# PX4FLOW2_1_CPU_X0.net
KiCad netlist of a schematic drawn in Altium Designer
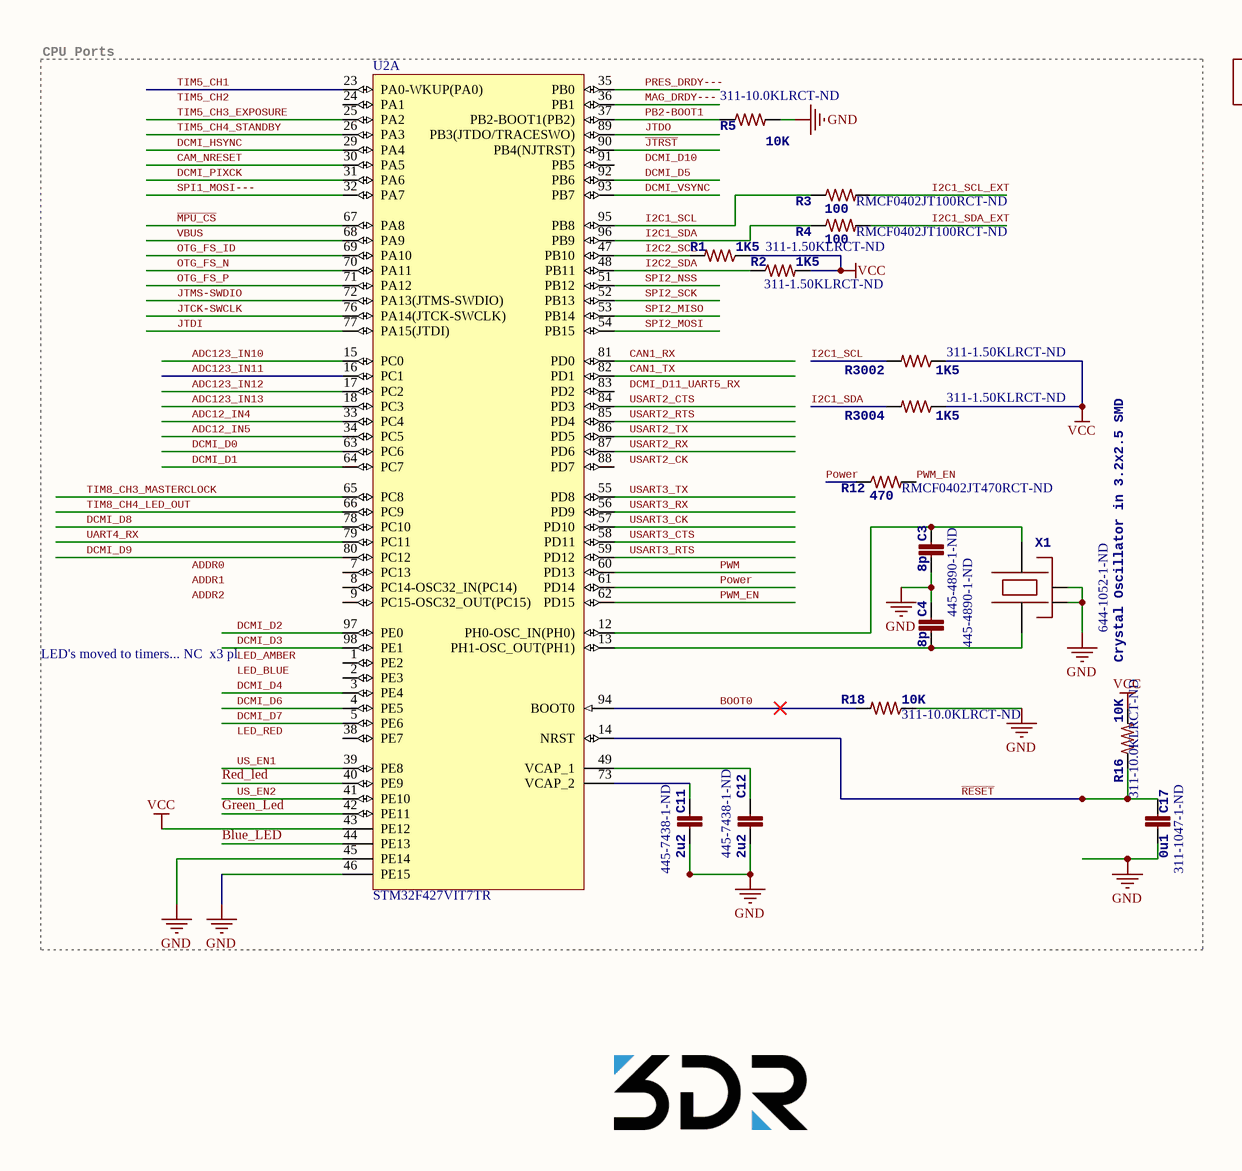
[diagram p0: PX4FLOW2.1_CPU_X0.SchDoc, left]
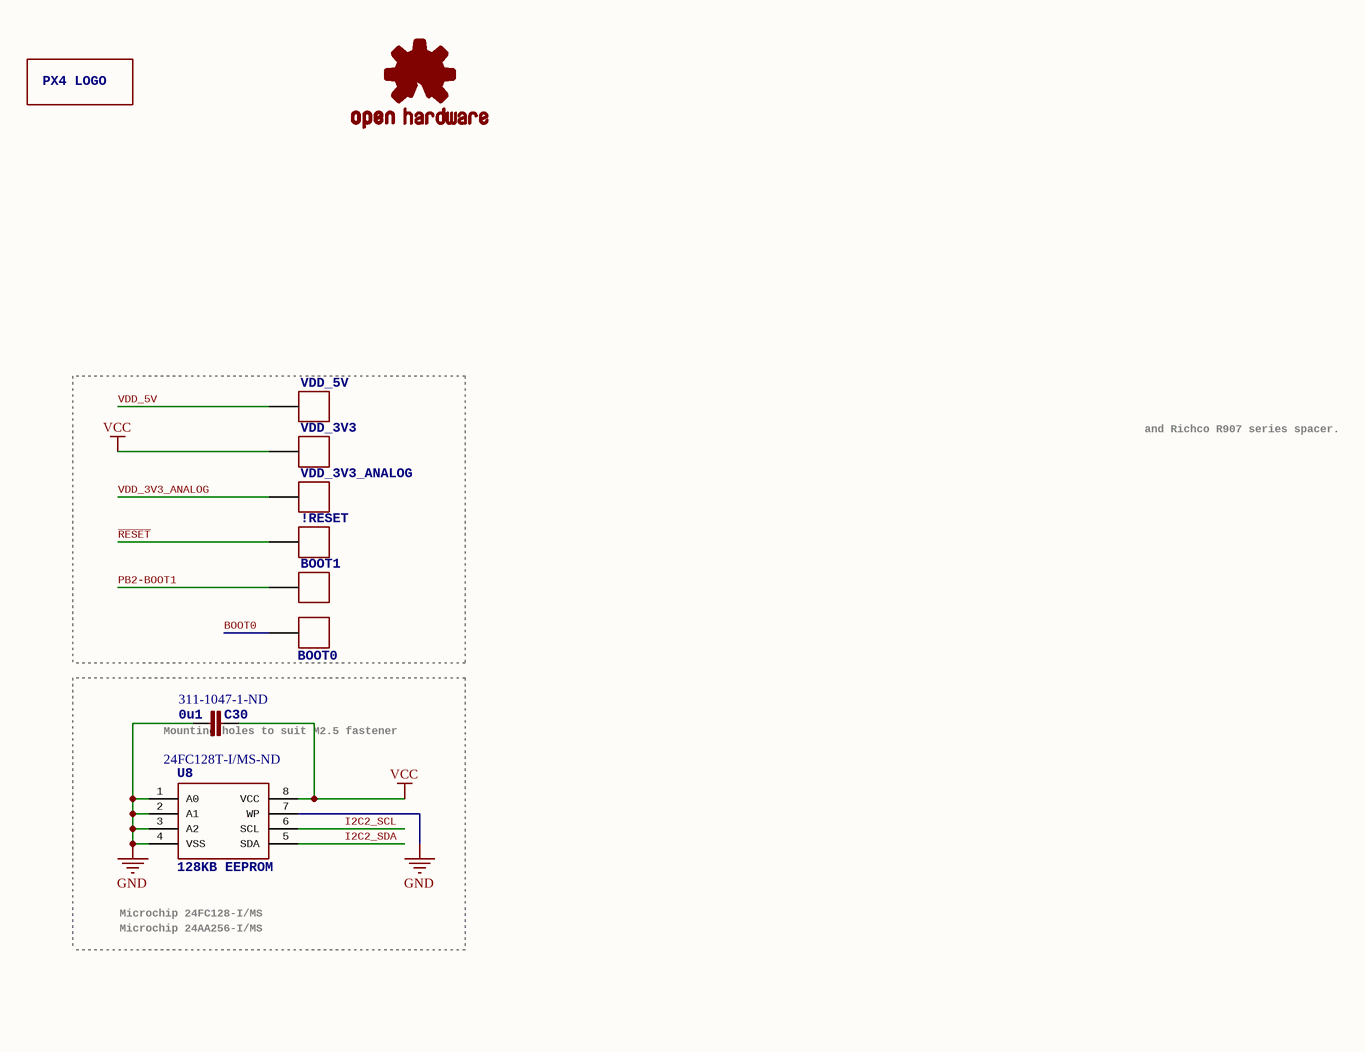
[diagram p1: PX4FLOW2.1_CPU_X0.SchDoc, right]

(export (version "E")
  (design (tool "Eeschema 10.0.6"))
  (components
    (comp (ref "!RESET") (value "PAD.04") (footprint "PAD.04X.04") (libsource (lib "") (part "PAD.04_1")))
    (comp (ref "3DR Logo")
      (value "DO NOT PLACE")
      (footprint "3DR_AU")
      (libsource (lib "3DR") (part "3DR_LOGO"))
    )
    (comp (ref "BOOT0")
      (value "PAD.05")
      (footprint "PAD.05X.05")
      (libsource (lib "pixhawk2") (part "PAD.05"))
    )
    (comp (ref "BOOT1")
      (value "PAD.04")
      (footprint "PAD.04X.04")
      (libsource (lib "pixhawk2") (part "PAD.04"))
    )
    (comp (ref "C3")
      (value "8p")
      (footprint "0402-CAP")
      (description "CAP CER 8PF 50V C0G 0402")
      (fields
        (field (name "PARTNO") "C1005C0G1H080C")
        (field (name "SUPPLIER PART NUMBER 1") "445-4890-1-ND")
        (field (name "3DR_PARTNO") "ECM0710")
      )
      (libsource (lib "pixhawk2") (part "CAP0402"))
    )
    (comp (ref "C4")
      (value "8p")
      (footprint "0402-CAP")
      (description "CAP CER 8PF 50V C0G 0402")
      (fields
        (field (name "PARTNO") "C1005C0G1H080C")
        (field (name "SUPPLIER PART NUMBER 1") "445-4890-1-ND")
        (field (name "3DR_PARTNO") "ECM0710")
      )
      (libsource (lib "pixhawk2") (part "CAP0402"))
    )
    (comp (ref "C11")
      (value "2u2")
      (footprint "0603-CAP")
      (description "Capacitor, 2.2uF, 16V, 10%, X6S, 0603, Ceramic")
      (fields
        (field (name "PARTNO") "C1608X6S1C225K080AC")
        (field (name "SUPPLIER PART NUMBER 1") "445-7438-1-ND")
        (field (name "3DR_PARTNO") "ECM0619")
      )
      (libsource (lib "pixhawk2") (part "CAP0603"))
    )
    (comp (ref "C12")
      (value "2u2")
      (footprint "0603-CAP")
      (description "Capacitor, 2.2uF, 16V, 10%, X6S, 0603, Ceramic")
      (fields
        (field (name "PARTNO") "C1608X6S1C225K080AC")
        (field (name "SUPPLIER PART NUMBER 1") "445-7438-1-ND")
        (field (name "3DR_PARTNO") "ECM0619")
      )
      (libsource (lib "pixhawk2") (part "CAP0603"))
    )
    (comp (ref "C17")
      (value "0u1")
      (footprint "C0402")
      (description "CapacitorStandard 0603 ceramic capacitor, and 0.1\" leaded capacitor.")
      (fields
        (field (name "PARTNO") "CC0402ZRY5V7BB104")
        (field (name "SUPPLIER PART NUMBER 1") "311-1047-1-ND")
      )
      (libsource (lib "") (part "CAP0402-CAP_1"))
    )
    (comp (ref "C30")
      (value "0u1")
      (footprint "C0402")
      (description "CapacitorStandard 0603 ceramic capacitor, and 0.1\" leaded capacitor.")
      (fields
        (field (name "PARTNO") "CC0402ZRY5V7BB104")
        (field (name "SUPPLIER PART NUMBER 1") "311-1047-1-ND")
      )
      (libsource (lib "pixhawk2") (part "CAP0402-CAP"))
    )
    (comp (ref "R1")
      (value "1K5")
      (footprint "R0402")
      (description "RES 1.5K OHM 1/16W 1% 0402 SMD")
      (fields
        (field (name "PARTNO") "RC0402FR-071K5L")
        (field (name "SUPPLIER PART NUMBER 1") "311-1.50KLRCT-ND")
        (field (name "3DR_PARTNO") "ECM0803")
      )
      (libsource (lib "pixhawk2") (part "RESISTOR0402-RES"))
    )
    (comp (ref "R2")
      (value "1K5")
      (footprint "R0402")
      (description "RES 1.5K OHM 1/16W 1% 0402 SMD")
      (fields
        (field (name "PARTNO") "RC0402FR-071K5L")
        (field (name "SUPPLIER PART NUMBER 1") "311-1.50KLRCT-ND")
        (field (name "3DR_PARTNO") "ECM0803")
      )
      (libsource (lib "pixhawk2") (part "RESISTOR0402-RES"))
    )
    (comp (ref "R3")
      (value "100")
      (footprint "R0402")
      (fields
        (field (name "PARTNO") "RMCF0402JT100R")
        (field (name "SUPPLIER PART NUMBER 1") "RMCF0402JT100RCT-ND")
      )
      (libsource (lib "pixhawk2") (part "RESISTOR0402-RES"))
    )
    (comp (ref "R4")
      (value "100")
      (footprint "R0402")
      (fields
        (field (name "PARTNO") "RMCF0402JT100R")
        (field (name "SUPPLIER PART NUMBER 1") "RMCF0402JT100RCT-ND")
      )
      (libsource (lib "pixhawk2") (part "RESISTOR0402-RES"))
    )
    (comp (ref "R5")
      (value "10K")
      (footprint "R0402")
      (description "RES 10K OHM 1/16W 1% 0402 SMD")
      (fields
        (field (name "PARTNO") "RC0402FR-0710KL")
        (field (name "SUPPLIER PART NUMBER 1") "311-10.0KLRCT-ND")
        (field (name "3DR_PARTNO") "ECM0800")
      )
      (libsource (lib "pixhawk2") (part "RESISTOR0402-RES"))
    )
    (comp (ref "R12")
      (value "470")
      (footprint "R0402")
      (fields
        (field (name "PARTNO") "RMCF0402JT100R")
        (field (name "SUPPLIER PART NUMBER 1") "RMCF0402JT470RCT-ND")
      )
      (libsource (lib "pixhawk2") (part "RESISTOR0402-RES"))
    )
    (comp (ref "R16")
      (value "10K")
      (footprint "R0402")
      (description "RES 10K OHM 1/16W 1% 0402 SMD")
      (fields
        (field (name "PARTNO") "RC0402FR-0710KL")
        (field (name "SUPPLIER PART NUMBER 1") "311-10.0KLRCT-ND")
        (field (name "3DR_PARTNO") "ECM0800")
      )
      (libsource (lib "pixhawk2") (part "RESISTOR0402-RES"))
    )
    (comp (ref "R18")
      (value "10K")
      (footprint "R0402")
      (description "RES 10K OHM 1/16W 1% 0402 SMD")
      (fields
        (field (name "PARTNO") "RC0402FR-0710KL")
        (field (name "SUPPLIER PART NUMBER 1") "311-10.0KLRCT-ND")
        (field (name "3DR_PARTNO") "ECM0800")
      )
      (libsource (lib "pixhawk2") (part "RESISTOR0402-RES"))
    )
    (comp (ref "R3002")
      (value "1K5")
      (footprint "R0402")
      (description "RES 1.5K OHM 1/16W 1% 0402 SMD")
      (fields
        (field (name "PARTNO") "RC0402FR-071K5L")
        (field (name "SUPPLIER PART NUMBER 1") "311-1.50KLRCT-ND")
        (field (name "3DR_PARTNO") "ECM0803")
      )
      (libsource (lib "pixhawk2") (part "RESISTOR0402-RES"))
    )
    (comp (ref "R3004")
      (value "1K5")
      (footprint "R0402")
      (description "RES 1.5K OHM 1/16W 1% 0402 SMD")
      (fields
        (field (name "PARTNO") "RC0402FR-071K5L")
        (field (name "SUPPLIER PART NUMBER 1") "311-1.50KLRCT-ND")
        (field (name "3DR_PARTNO") "ECM0803")
      )
      (libsource (lib "3DR") (part "R0402"))
    )
    (comp (ref "U$9")
      (value "PX4-LOGO-20MM")
      (footprint "PX4-LOGO-20MM")
      (fields (field (name "PX4LOGO") "PX4 LOGO"))
      (libsource (lib "pixhawk2") (part "PX4-LOGO-20MM"))
    )
    (comp (ref "U$10")
      (value "OSHW-LOGOS")
      (footprint "OSHW-LOGO-S")
      (libsource (lib "pixhawk2") (part "OSHW-LOGOS"))
    )
    (comp (ref "U2")
      (value "STM32F427VIT7TR")
      (footprint "STM-LQFP100_N")
      (fields (field (name "MANUFACTURER") "STMicroelectronics"))
      (libsource (lib "STMicroelectronics STM32 F4") (part "STM32F427VIT7TR"))
    )
    (comp (ref "U8")
      (value "128KB EEPROM")
      (footprint "MSOP-8")
      (fields
        (field (name "PARTNO") "24FC128-I/MS")
        (field (name "SUPPLIER PART NUMBER 1") "24FC128T-I/MS-ND")
      )
      (libsource (lib "pixhawk2") (part "EEPROM-I2CMSOP"))
    )
    (comp (ref "VDD_3V3")
      (value "PAD.04")
      (footprint "PAD.04X.04")
      (libsource (lib "pixhawk2") (part "PAD.04"))
    )
    (comp (ref "VDD_3V3_ANALOG")
      (value "PAD.04")
      (footprint "PAD.04X.04")
      (libsource (lib "pixhawk2") (part "PAD.04"))
    )
    (comp (ref "VDD_5V")
      (value "PAD.04")
      (footprint "PAD.04X.04")
      (libsource (lib "pixhawk2") (part "PAD.04"))
    )
    (comp (ref "X1")
      (value "Crystal Oscillator in 3.2x2.5 SMD")
      (footprint "OSCILLATOR-3.2X2.5")
      (description "CRYSTAL 24MHZ 8PF SMD")
      (fields
        (field (name "SUPPLIER PART NUMBER 1") "644-1052-1-ND")
        (field (name "3DR_PARTNO") "ECM0708")
        (field (name "PARTNO") "NX3225SA-24.000MHZ-STD-CSR-1")
      )
      (libsource (lib "pixhawk2") (part "OSCILLATOR-3.2X2.5"))
    )
  )
  (nets
    (net (code "1") (name "/ADC12_IN4") (class "Default")
      (node (ref "U2") (pin "33") (pinfunction "PC4_33") (pintype "bidirectional"))
    )
    (net (code "2") (name "/ADC12_IN5") (class "Default")
      (node (ref "U2") (pin "34") (pinfunction "PC5_34") (pintype "bidirectional"))
    )
    (net (code "3") (name "/ADC123_IN10") (class "Default")
      (node (ref "U2") (pin "15") (pinfunction "PC0_15") (pintype "bidirectional"))
    )
    (net (code "4") (name "/ADC123_IN11") (class "Default")
      (node (ref "U2") (pin "16") (pinfunction "PC1_16") (pintype "bidirectional"))
    )
    (net (code "5") (name "/ADC123_IN12") (class "Default")
      (node (ref "U2") (pin "17") (pinfunction "PC2_17") (pintype "bidirectional"))
    )
    (net (code "6") (name "/ADC123_IN13") (class "Default")
      (node (ref "U2") (pin "18") (pinfunction "PC3_18") (pintype "bidirectional"))
    )
    (net (code "10") (name "/BOOT0") (class "Default")
      (node (ref "BOOT0") (pin "P$1") (pinfunction "P$1_P$1") (pintype "passive"))
      (node (ref "R18") (pin "2") (pinfunction "2_2") (pintype "passive"))
      (node (ref "U2") (pin "94") (pinfunction "BOOT0_94") (pintype "input"))
    )
    (net (code "11") (name "/Blue_LED") (class "Default")
      (node (ref "U2") (pin "44") (pinfunction "PE13_44") (pintype "power_in"))
    )
    (net (code "12") (name "/CAM_NRESET") (class "Default")
      (node (ref "U2") (pin "30") (pinfunction "PA5_30") (pintype "bidirectional"))
    )
    (net (code "13") (name "/CAN1_RX") (class "Default")
      (node (ref "U2") (pin "81") (pinfunction "PD0_81") (pintype "bidirectional"))
    )
    (net (code "14") (name "/CAN1_TX") (class "Default")
      (node (ref "U2") (pin "82") (pinfunction "PD1_82") (pintype "bidirectional"))
    )
    (net (code "15") (name "/DCMI_D0") (class "Default")
      (node (ref "U2") (pin "63") (pinfunction "PC6_63") (pintype "bidirectional"))
    )
    (net (code "16") (name "/DCMI_D1") (class "Default")
      (node (ref "U2") (pin "64") (pinfunction "PC7_64") (pintype "bidirectional"))
    )
    (net (code "17") (name "/DCMI_D2") (class "Default")
      (node (ref "U2") (pin "97") (pinfunction "PE0_97") (pintype "bidirectional"))
    )
    (net (code "18") (name "/DCMI_D3") (class "Default")
      (node (ref "U2") (pin "98") (pinfunction "PE1_98") (pintype "bidirectional"))
    )
    (net (code "19") (name "/DCMI_D4") (class "Default")
      (node (ref "U2") (pin "3") (pinfunction "PE4_3") (pintype "bidirectional"))
    )
    (net (code "20") (name "/DCMI_D5") (class "Default")
      (node (ref "U2") (pin "92") (pinfunction "PB6_92") (pintype "bidirectional"))
    )
    (net (code "21") (name "/DCMI_D6") (class "Default")
      (node (ref "U2") (pin "4") (pinfunction "PE5_4") (pintype "bidirectional"))
    )
    (net (code "22") (name "/DCMI_D7") (class "Default")
      (node (ref "U2") (pin "5") (pinfunction "PE6_5") (pintype "bidirectional"))
    )
    (net (code "23") (name "/DCMI_D8") (class "Default")
      (node (ref "U2") (pin "78") (pinfunction "PC10_78") (pintype "bidirectional"))
    )
    (net (code "24") (name "/DCMI_D9") (class "Default")
      (node (ref "U2") (pin "80") (pinfunction "PC12_80") (pintype "bidirectional"))
    )
    (net (code "27") (name "/DCMI_HSYNC") (class "Default")
      (node (ref "U2") (pin "29") (pinfunction "PA4_29") (pintype "bidirectional"))
    )
    (net (code "28") (name "/DCMI_PIXCK") (class "Default")
      (node (ref "U2") (pin "31") (pinfunction "PA6_31") (pintype "bidirectional"))
    )
    (net (code "29") (name "/DCMI_VSYNC") (class "Default")
      (node (ref "U2") (pin "93") (pinfunction "PB7_93") (pintype "bidirectional"))
    )
    (net (code "30") (name "/Green_Led") (class "Default")
      (node (ref "U2") (pin "42") (pinfunction "PE11_42") (pintype "bidirectional"))
    )
    (net (code "31") (name "/I2C1_SCL") (class "Default")
      (node (ref "R3") (pin "1") (pinfunction "1_1") (pintype "passive"))
      (node (ref "R3002") (pin "2") (pinfunction "2_2") (pintype "passive"))
      (node (ref "U2") (pin "95") (pinfunction "PB8_95") (pintype "bidirectional"))
    )
    (net (code "32") (name "/I2C1_SCL_EXT") (class "Default")
      (node (ref "R3") (pin "2") (pinfunction "2_2") (pintype "passive"))
    )
    (net (code "33") (name "/I2C1_SDA") (class "Default")
      (node (ref "R3004") (pin "2") (pinfunction "2_2") (pintype "passive"))
      (node (ref "R4") (pin "1") (pinfunction "1_1") (pintype "passive"))
      (node (ref "U2") (pin "96") (pinfunction "PB9_96") (pintype "bidirectional"))
    )
    (net (code "34") (name "/I2C1_SDA_EXT") (class "Default")
      (node (ref "R4") (pin "2") (pinfunction "2_2") (pintype "passive"))
    )
    (net (code "35") (name "/I2C2_SCL") (class "Default")
      (node (ref "R1") (pin "2") (pinfunction "2_2") (pintype "passive"))
      (node (ref "U2") (pin "47") (pinfunction "PB10_47") (pintype "bidirectional"))
      (node (ref "U8") (pin "6") (pinfunction "SCL_6") (pintype "passive"))
    )
    (net (code "36") (name "/I2C2_SDA") (class "Default")
      (node (ref "R2") (pin "1") (pinfunction "1_1") (pintype "passive"))
      (node (ref "U2") (pin "48") (pinfunction "PB11_48") (pintype "bidirectional"))
      (node (ref "U8") (pin "5") (pinfunction "SDA_5") (pintype "passive"))
    )
    (net (code "37") (name "/JTCK-SWCLK") (class "Default")
      (node (ref "U2") (pin "76") (pinfunction "PA14(JTCK-SWCLK)_76") (pintype "bidirectional"))
    )
    (net (code "38") (name "/JTDI") (class "Default")
      (node (ref "U2") (pin "77") (pinfunction "PA15(JTDI)_77") (pintype "bidirectional"))
    )
    (net (code "39") (name "/JTDO") (class "Default")
      (node (ref "U2") (pin "89") (pinfunction "PB3(JTDO/TRACESWO)_89") (pintype "bidirectional"))
    )
    (net (code "40") (name "/JTMS-SWDIO") (class "Default")
      (node (ref "U2") (pin "72") (pinfunction "PA13(JTMS-SWDIO)_72") (pintype "bidirectional"))
    )
    (net (code "44") (name "/MAG_DRDY---") (class "Default")
      (node (ref "U2") (pin "36") (pinfunction "PB1_36") (pintype "bidirectional"))
    )
    (net (code "45") (name "/OTG_FS_ID") (class "Default")
      (node (ref "U2") (pin "69") (pinfunction "PA10_69") (pintype "bidirectional"))
    )
    (net (code "46") (name "/OTG_FS_N") (class "Default")
      (node (ref "U2") (pin "70") (pinfunction "PA11_70") (pintype "bidirectional"))
    )
    (net (code "47") (name "/OTG_FS_P") (class "Default")
      (node (ref "U2") (pin "71") (pinfunction "PA12_71") (pintype "bidirectional"))
    )
    (net (code "48") (name "/PB2-BOOT1") (class "Default")
      (node (ref "BOOT1") (pin "P$1") (pinfunction "P$1_P$1") (pintype "passive"))
      (node (ref "R5") (pin "1") (pinfunction "1_1") (pintype "passive"))
      (node (ref "U2") (pin "37") (pinfunction "PB2-BOOT1(PB2)_37") (pintype "bidirectional"))
    )
    (net (code "49") (name "/PRES_DRDY---") (class "Default")
      (node (ref "U2") (pin "35") (pinfunction "PB0_35") (pintype "bidirectional"))
    )
    (net (code "50") (name "/PWM") (class "Default")
      (node (ref "U2") (pin "60") (pinfunction "PD13_60") (pintype "bidirectional"))
    )
    (net (code "51") (name "/PWM_EN") (class "Default")
      (node (ref "R12") (pin "2") (pinfunction "2_2") (pintype "passive"))
      (node (ref "U2") (pin "62") (pinfunction "PD15_62") (pintype "bidirectional"))
    )
    (net (code "52") (name "/Power") (class "Default")
      (node (ref "R12") (pin "1") (pinfunction "1_1") (pintype "passive"))
      (node (ref "U2") (pin "61") (pinfunction "PD14_61") (pintype "bidirectional"))
    )
    (net (code "53") (name "/Red_led") (class "Default")
      (node (ref "U2") (pin "40") (pinfunction "PE9_40") (pintype "bidirectional"))
    )
    (net (code "54") (name "/SPI1_MOSI---") (class "Default")
      (node (ref "U2") (pin "32") (pinfunction "PA7_32") (pintype "bidirectional"))
    )
    (net (code "55") (name "/SPI2_MISO") (class "Default")
      (node (ref "U2") (pin "53") (pinfunction "PB14_53") (pintype "bidirectional"))
    )
    (net (code "56") (name "/SPI2_MOSI") (class "Default")
      (node (ref "U2") (pin "54") (pinfunction "PB15_54") (pintype "bidirectional"))
    )
    (net (code "57") (name "/SPI2_NSS") (class "Default")
      (node (ref "U2") (pin "51") (pinfunction "PB12_51") (pintype "bidirectional"))
    )
    (net (code "58") (name "/SPI2_SCK") (class "Default")
      (node (ref "U2") (pin "52") (pinfunction "PB13_52") (pintype "bidirectional"))
    )
    (net (code "59") (name "/TIM5_CH1") (class "Default")
      (node (ref "U2") (pin "23") (pinfunction "PA0-WKUP(PA0)_23") (pintype "bidirectional"))
    )
    (net (code "61") (name "/TIM5_CH3_EXPOSURE") (class "Default")
      (node (ref "U2") (pin "25") (pinfunction "PA2_25") (pintype "bidirectional"))
    )
    (net (code "62") (name "/TIM5_CH4_STANDBY") (class "Default")
      (node (ref "U2") (pin "26") (pinfunction "PA3_26") (pintype "bidirectional"))
    )
    (net (code "63") (name "/TIM8_CH3_MASTERCLOCK") (class "Default")
      (node (ref "U2") (pin "65") (pinfunction "PC8_65") (pintype "bidirectional"))
    )
    (net (code "64") (name "/TIM8_CH4_LED_OUT") (class "Default")
      (node (ref "U2") (pin "66") (pinfunction "PC9_66") (pintype "bidirectional"))
    )
    (net (code "65") (name "/UART4_RX") (class "Default")
      (node (ref "U2") (pin "79") (pinfunction "PC11_79") (pintype "bidirectional"))
    )
    (net (code "67") (name "/USART2_CTS") (class "Default")
      (node (ref "U2") (pin "84") (pinfunction "PD3_84") (pintype "bidirectional"))
    )
    (net (code "68") (name "/USART2_RTS") (class "Default")
      (node (ref "U2") (pin "85") (pinfunction "PD4_85") (pintype "bidirectional"))
    )
    (net (code "69") (name "/USART2_RX") (class "Default")
      (node (ref "U2") (pin "87") (pinfunction "PD6_87") (pintype "bidirectional"))
    )
    (net (code "70") (name "/USART2_TX") (class "Default")
      (node (ref "U2") (pin "86") (pinfunction "PD5_86") (pintype "bidirectional"))
    )
    (net (code "71") (name "/USART3_CK") (class "Default")
      (node (ref "U2") (pin "57") (pinfunction "PD10_57") (pintype "bidirectional"))
    )
    (net (code "72") (name "/USART3_CTS") (class "Default")
      (node (ref "U2") (pin "58") (pinfunction "PD11_58") (pintype "bidirectional"))
    )
    (net (code "73") (name "/USART3_RTS") (class "Default")
      (node (ref "U2") (pin "59") (pinfunction "PD12_59") (pintype "bidirectional"))
    )
    (net (code "74") (name "/USART3_RX") (class "Default")
      (node (ref "U2") (pin "56") (pinfunction "PD9_56") (pintype "bidirectional"))
    )
    (net (code "75") (name "/USART3_TX") (class "Default")
      (node (ref "U2") (pin "55") (pinfunction "PD8_55") (pintype "bidirectional"))
    )
    (net (code "76") (name "/US_EN1") (class "Default")
      (node (ref "U2") (pin "39") (pinfunction "PE8_39") (pintype "bidirectional"))
    )
    (net (code "77") (name "/US_EN2") (class "Default")
      (node (ref "U2") (pin "41") (pinfunction "PE10_41") (pintype "bidirectional"))
    )
    (net (code "78") (name "/VBUS") (class "Default")
      (node (ref "U2") (pin "68") (pinfunction "PA9_68") (pintype "bidirectional"))
    )
    (net (code "79") (name "/VDD_3V3_ANALOG") (class "Default")
      (node (ref "VDD_3V3_ANALOG") (pin "P$1") (pinfunction "P$1_P$1") (pintype "passive"))
    )
    (net (code "80") (name "/VDD_5V") (class "Default")
      (node (ref "VDD_5V") (pin "P$1") (pinfunction "P$1_P$1") (pintype "passive"))
    )
    (net (code "81") (name "/~{JTRST}") (class "Default")
      (node (ref "U2") (pin "90") (pinfunction "PB4(NJTRST)_90") (pintype "bidirectional"))
    )
    (net (code "82") (name "/~{MPU_CS}") (class "Default")
      (node (ref "U2") (pin "67") (pinfunction "PA8_67") (pintype "bidirectional"))
    )
    (net (code "83") (name "/~{RESET}") (class "Default")
      (node (ref "!RESET") (pin "P1") (pinfunction "P1_P1") (pintype "passive"))
      (node (ref "C17") (pin "2") (pinfunction "2_2") (pintype "passive"))
      (node (ref "R16") (pin "1") (pinfunction "1_1") (pintype "passive"))
      (node (ref "U2") (pin "14") (pinfunction "NRST_14") (pintype "bidirectional"))
    )
    (net (code "84") (name "GND") (class "Default")
      (node (ref "C11") (pin "P$2") (pinfunction "2_P$2") (pintype "passive"))
      (node (ref "C12") (pin "P$2") (pinfunction "2_P$2") (pintype "passive"))
      (node (ref "C17") (pin "1") (pinfunction "1_1") (pintype "passive"))
      (node (ref "C3") (pin "P$2") (pinfunction "2_P$2") (pintype "passive"))
      (node (ref "C30") (pin "2") (pinfunction "2_2") (pintype "passive"))
      (node (ref "C4") (pin "P$1") (pinfunction "1_P$1") (pintype "passive"))
      (node (ref "R18") (pin "1") (pinfunction "1_1") (pintype "passive"))
      (node (ref "R5") (pin "2") (pinfunction "2_2") (pintype "passive"))
      (node (ref "U2") (pin "45") (pinfunction "PE14_45") (pintype "power_in"))
      (node (ref "U2") (pin "46") (pinfunction "PE15_46") (pintype "power_in"))
      (node (ref "U8") (pin "1") (pinfunction "A0_1") (pintype "power_in"))
      (node (ref "U8") (pin "2") (pinfunction "A1_2") (pintype "power_in"))
      (node (ref "U8") (pin "3") (pinfunction "A2_3") (pintype "power_in"))
      (node (ref "U8") (pin "4") (pinfunction "VSS_4") (pintype "power_in"))
      (node (ref "U8") (pin "7") (pinfunction "WP_7") (pintype "power_in"))
      (node (ref "X1") (pin "2") (pinfunction "NC_2_2") (pintype "power_in"))
      (node (ref "X1") (pin "4") (pinfunction "NC_4_4") (pintype "power_in"))
    )
    (net (code "85") (name "Net-(C3-1)") (class "Default")
      (node (ref "C3") (pin "P$1") (pinfunction "1_P$1") (pintype "passive"))
      (node (ref "U2") (pin "12") (pinfunction "PH0-OSC_IN(PH0)_12") (pintype "bidirectional"))
      (node (ref "X1") (pin "3") (pinfunction "3_3") (pintype "passive"))
    )
    (net (code "86") (name "Net-(C4-2)") (class "Default")
      (node (ref "C4") (pin "P$2") (pinfunction "2_P$2") (pintype "passive"))
      (node (ref "U2") (pin "13") (pinfunction "PH1-OSC_OUT(PH1)_13") (pintype "bidirectional"))
      (node (ref "X1") (pin "1") (pinfunction "1_1") (pintype "passive"))
    )
    (net (code "87") (name "Net-(C11-1)") (class "Default")
      (node (ref "C11") (pin "P$1") (pinfunction "1_P$1") (pintype "passive"))
      (node (ref "U2") (pin "73") (pinfunction "VCAP_2_73") (pintype "power_in"))
    )
    (net (code "88") (name "Net-(C12-1)") (class "Default")
      (node (ref "C12") (pin "P$1") (pinfunction "1_P$1") (pintype "passive"))
      (node (ref "U2") (pin "49") (pinfunction "VCAP_1_49") (pintype "power_in"))
    )
    (net (code "89") (name "VCC") (class "Default")
      (node (ref "C30") (pin "1") (pinfunction "1_1") (pintype "passive"))
      (node (ref "R1") (pin "1") (pinfunction "1_1") (pintype "passive"))
      (node (ref "R16") (pin "2") (pinfunction "2_2") (pintype "passive"))
      (node (ref "R2") (pin "2") (pinfunction "2_2") (pintype "passive"))
      (node (ref "R3002") (pin "1") (pinfunction "1_1") (pintype "passive"))
      (node (ref "R3004") (pin "1") (pinfunction "1_1") (pintype "passive"))
      (node (ref "U2") (pin "43") (pinfunction "PE12_43") (pintype "power_in"))
      (node (ref "U8") (pin "8") (pinfunction "VCC_8") (pintype "power_in"))
      (node (ref "VDD_3V3") (pin "P$1") (pinfunction "P$1_P$1") (pintype "passive"))
    )
    (net (code "90") (name "unconnected-(U2A-PA1-Pad24)") (class "Default")
      (node (ref "U2") (pin "24") (pinfunction "PA1_24") (pintype "bidirectional"))
    )
    (net (code "91") (name "unconnected-(U2A-PB5-Pad91)") (class "Default")
      (node (ref "U2") (pin "91") (pinfunction "PB5_91") (pintype "bidirectional"))
    )
    (net (code "92") (name "unconnected-(U2A-PC13-Pad7)") (class "Default")
      (node (ref "U2") (pin "7") (pinfunction "PC13_7") (pintype "bidirectional"))
    )
    (net (code "93") (name "unconnected-(U2A-PC14-OSC32_IN(PC14)-Pad8)") (class "Default")
      (node (ref "U2") (pin "8") (pinfunction "PC14-OSC32_IN(PC14)_8") (pintype "bidirectional"))
    )
    (net (code "94") (name "unconnected-(U2A-PC15-OSC32_OUT(PC15)-Pad9)") (class "Default")
      (node (ref "U2") (pin "9") (pinfunction "PC15-OSC32_OUT(PC15)_9") (pintype "bidirectional"))
    )
    (net (code "95") (name "unconnected-(U2A-PD2-Pad83)") (class "Default")
      (node (ref "U2") (pin "83") (pinfunction "PD2_83") (pintype "bidirectional"))
    )
    (net (code "96") (name "unconnected-(U2A-PD7-Pad88)") (class "Default")
      (node (ref "U2") (pin "88") (pinfunction "PD7_88") (pintype "bidirectional"))
    )
    (net (code "97") (name "unconnected-(U2A-PE2-Pad1)") (class "Default")
      (node (ref "U2") (pin "1") (pinfunction "PE2_1") (pintype "bidirectional"))
    )
    (net (code "98") (name "unconnected-(U2A-PE3-Pad2)") (class "Default")
      (node (ref "U2") (pin "2") (pinfunction "PE3_2") (pintype "bidirectional"))
    )
    (net (code "99") (name "unconnected-(U2A-PE7-Pad38)") (class "Default")
      (node (ref "U2") (pin "38") (pinfunction "PE7_38") (pintype "bidirectional"))
    )
  )
)
